# OnOnfre_dual_rev2.net
KiCad netlist of a schematic drawn in EAGLE
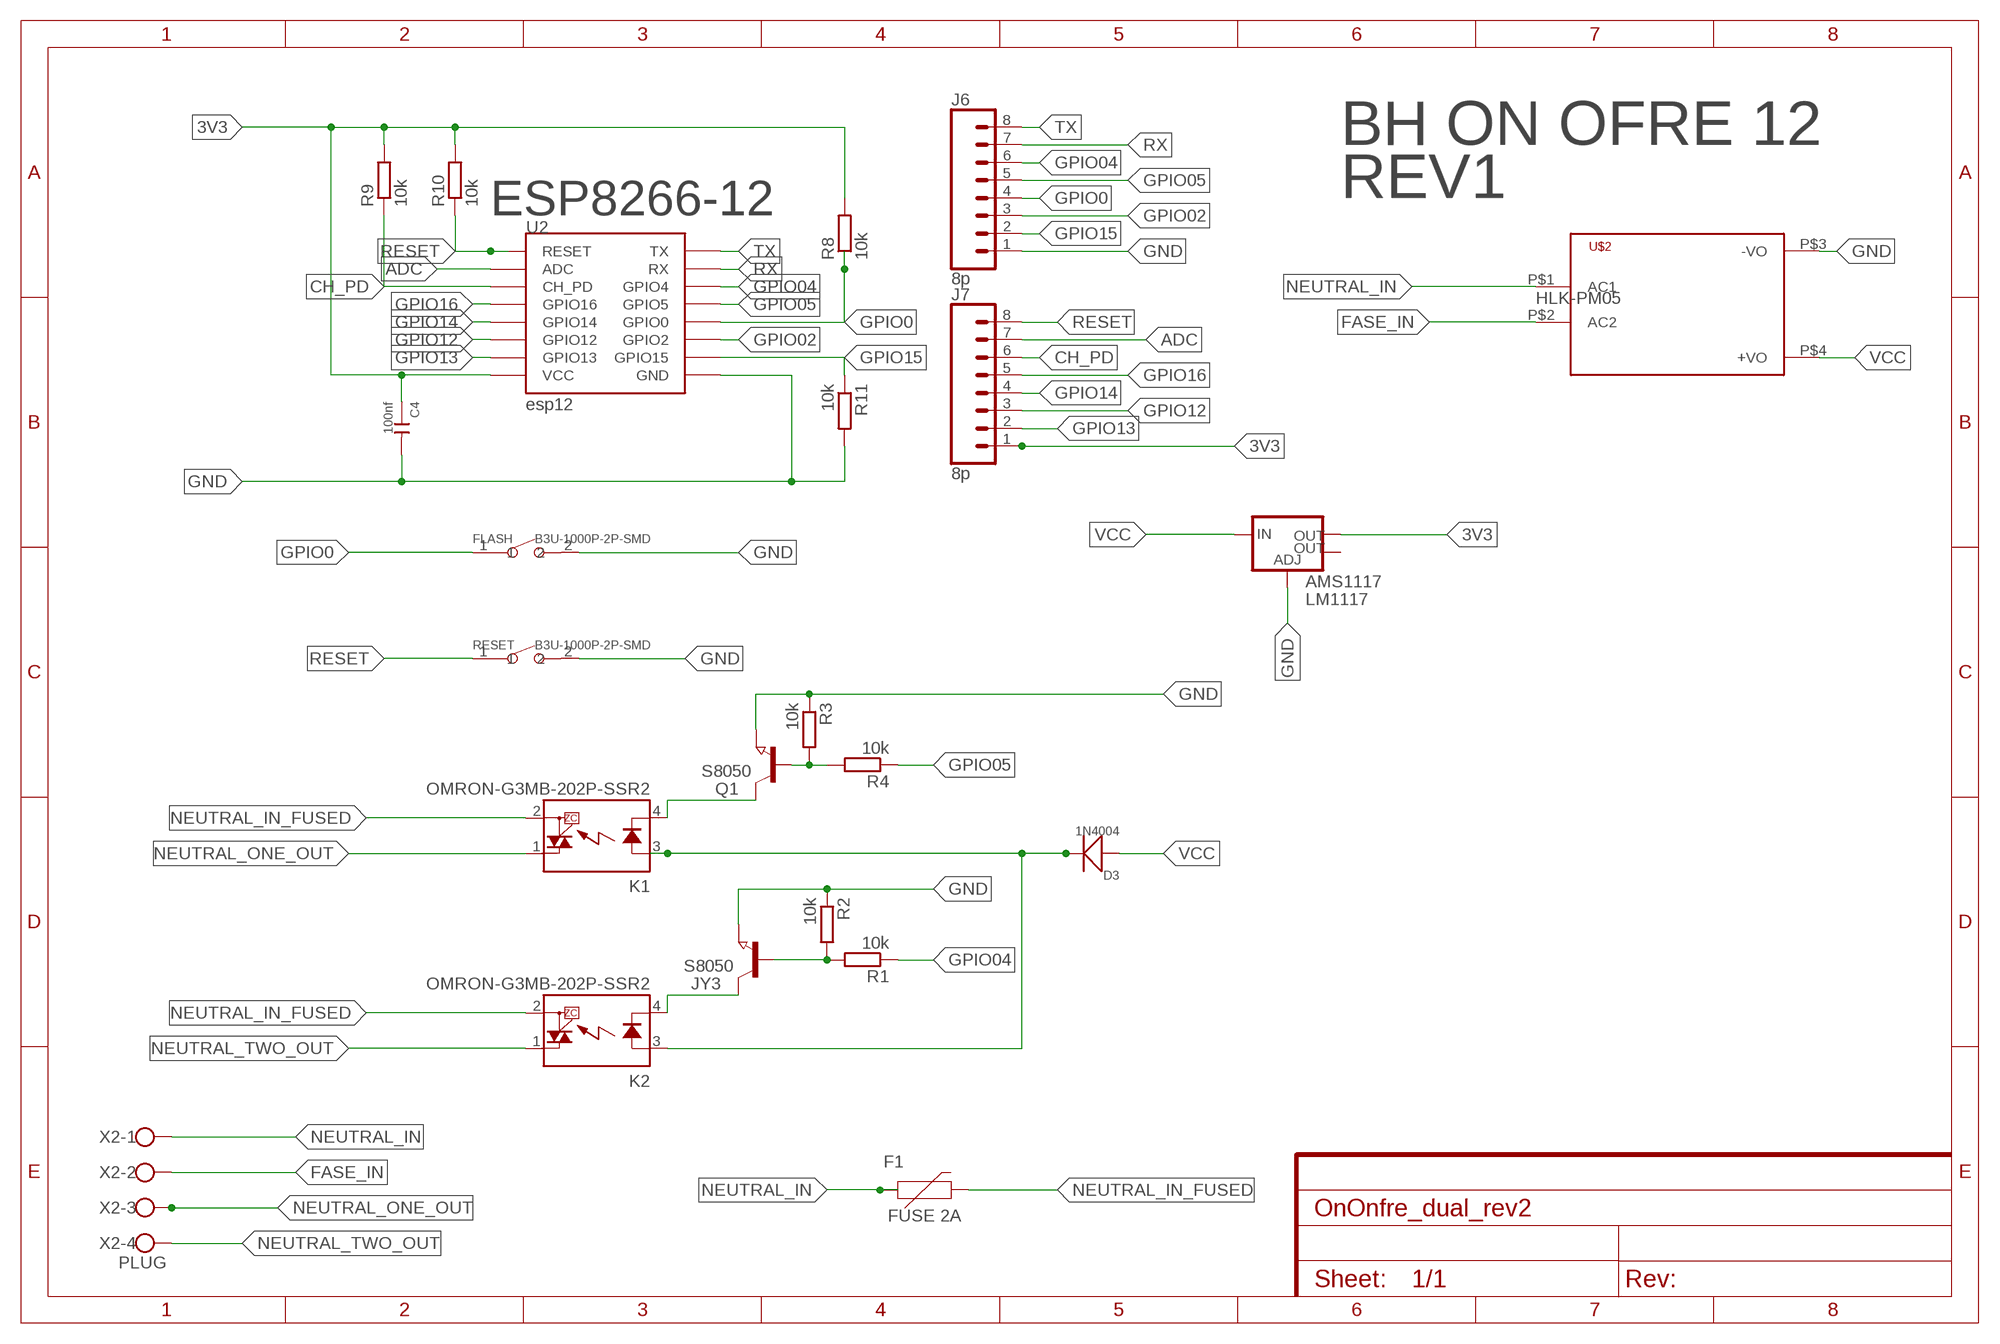
[diagram p0: schematic, sheet 1]

(export (version "E")
  (design (tool "Eeschema 10.0.6"))
  (components
    (comp (ref "AMS1117")
      (value "LM1117")
      (footprint "eagle-import:SOT223")
      (libsource (lib "eagle-import") (part "V_REG_LM1117SOT223"))
    )
    (comp (ref "C4")
      (value "100nf")
      (footprint "eagle-import:C0805")
      (fields (field (name "MPN") "CC0805KRX7R9BB104"))
      (libsource (lib "eagle-import") (part "CERAMIC-100NF-50V-10%-X7R(0805)"))
    )
    (comp (ref "D3")
      (value "1N4004")
      (footprint "eagle-import:DO-214AC")
      (fields (field (name "MPN") "1N4007"))
      (libsource (lib "eagle-import") (part "DIODE-GEN-PURPOSE-1KV-1A(DO-214AC)"))
    )
    (comp (ref "F1")
      (value "FUSE 2A")
      (footprint "eagle-import:PTH")
      (libsource (lib "eagle-import") (part "PPTC_PTH"))
    )
    (comp (ref "FLASH")
      (value "B3U-1000P-2P-SMD")
      (footprint "eagle-import:SW2-2.6-3.0X2.5X1.2+0.4MM")
      (libsource (lib "eagle-import") (part "SMD-BUTTON(2P-3.0X2.5X1.2+0.4MM)-B3U-1000P-2P-SMD"))
    )
    (comp (ref "J6")
      (value "8p")
      (footprint "eagle-import:1X08")
      (libsource (lib "eagle-import") (part "CONN_08{dblquote}"))
    )
    (comp (ref "J7")
      (value "8p")
      (footprint "eagle-import:1X08")
      (libsource (lib "eagle-import") (part "CONN_08{dblquote}"))
    )
    (comp (ref "JY3")
      (value "S8050")
      (footprint "eagle-import:SOT23")
      (libsource (lib "eagle-import") (part "NPN-TRANSISTOR_SOT23"))
    )
    (comp (ref "K1")
      (value "OMRON-G3MB-202P-SSR2")
      (footprint "eagle-import:OMRON-G3MB-202P-SSR")
      (fields (field (name "MPN") "S202S02F"))
      (libsource (lib "eagle-import") (part "OMRON-G3MB-202P-SSR2"))
    )
    (comp (ref "K2")
      (value "OMRON-G3MB-202P-SSR2")
      (footprint "eagle-import:OMRON-G3MB-202P-SSR")
      (fields (field (name "MPN") "S202S02F"))
      (libsource (lib "eagle-import") (part "OMRON-G3MB-202P-SSR2"))
    )
    (comp (ref "Q1")
      (value "S8050")
      (footprint "eagle-import:SOT23")
      (libsource (lib "eagle-import") (part "NPN-TRANSISTOR_SOT23"))
    )
    (comp (ref "R1")
      (value "10k")
      (footprint "eagle-import:R0603")
      (libsource (lib "eagle-import") (part "R-EU_R0603"))
    )
    (comp (ref "R2")
      (value "10k")
      (footprint "eagle-import:R0603")
      (libsource (lib "eagle-import") (part "R-EU_R0603"))
    )
    (comp (ref "R3")
      (value "10k")
      (footprint "eagle-import:R0603")
      (libsource (lib "eagle-import") (part "R-EU_R0603"))
    )
    (comp (ref "R4")
      (value "10k")
      (footprint "eagle-import:R0603")
      (libsource (lib "eagle-import") (part "R-EU_R0603"))
    )
    (comp (ref "R8")
      (value "10k")
      (footprint "eagle-import:R0603")
      (libsource (lib "eagle-import") (part "R-EU_R0603"))
    )
    (comp (ref "R9")
      (value "10k")
      (footprint "eagle-import:R0603")
      (libsource (lib "eagle-import") (part "R-EU_R0603"))
    )
    (comp (ref "R10")
      (value "10k")
      (footprint "eagle-import:R0603")
      (libsource (lib "eagle-import") (part "R-EU_R0603"))
    )
    (comp (ref "R11")
      (value "10k")
      (footprint "eagle-import:R0603")
      (libsource (lib "eagle-import") (part "R-EU_R0603"))
    )
    (comp (ref "RESET")
      (value "B3U-1000P-2P-SMD")
      (footprint "eagle-import:SW2-2.6-3.0X2.5X1.2+0.4MM")
      (libsource (lib "eagle-import") (part "SMD-BUTTON(2P-3.0X2.5X1.2+0.4MM)-B3U-1000P-2P-SMD"))
    )
    (comp (ref "U$2")
      (value "HKLPM01")
      (footprint "eagle-import:HKLPM01")
      (libsource (lib "eagle-import") (part "HKLPM01"))
    )
    (comp (ref "U2")
      (value "esp12")
      (footprint "eagle-import:ESP12-SMD")
      (libsource (lib "eagle-import") (part "ESP12SMD"))
    )
    (comp (ref "X2")
      (value "PLUG")
      (footprint "eagle-import:W237-4")
      (libsource (lib "eagle-import") (part "W237-4"))
    )
  )
  (nets
    (net (code "1") (name "3V3") (class "Default")
      (node (ref "AMS1117") (pin "2") (pinfunction "OUT_2") (pintype "output"))
      (node (ref "C4") (pin "1") (pinfunction "1_1") (pintype "passive"))
      (node (ref "J7") (pin "1") (pinfunction "1_1") (pintype "passive"))
      (node (ref "R10") (pin "2") (pinfunction "2_2") (pintype "passive"))
      (node (ref "R8") (pin "2") (pinfunction "2_2") (pintype "passive"))
      (node (ref "R9") (pin "2") (pinfunction "2_2") (pintype "passive"))
      (node (ref "U2") (pin "VCC") (pinfunction "VCC_VCC") (pintype "bidirectional"))
    )
    (net (code "2") (name "ADC") (class "Default")
      (node (ref "J7") (pin "7") (pinfunction "7_7") (pintype "passive"))
      (node (ref "U2") (pin "ADC") (pinfunction "ADC_ADC") (pintype "bidirectional"))
    )
    (net (code "3") (name "CH_PD") (class "Default")
      (node (ref "J7") (pin "6") (pinfunction "6_6") (pintype "passive"))
      (node (ref "R9") (pin "1") (pinfunction "1_1") (pintype "passive"))
      (node (ref "U2") (pin "CH_PD") (pinfunction "CH_PD_CH_PD") (pintype "bidirectional"))
    )
    (net (code "4") (name "FASE_IN") (class "Default")
      (node (ref "U$2") (pin "P$2") (pinfunction "AC2_P$2") (pintype "bidirectional"))
      (node (ref "X2") (pin "2") (pinfunction "KL_2") (pintype "passive"))
    )
    (net (code "5") (name "GND") (class "Default")
      (node (ref "AMS1117") (pin "1") (pinfunction "ADJ_1") (pintype "input"))
      (node (ref "C4") (pin "2") (pinfunction "2_2") (pintype "passive"))
      (node (ref "FLASH") (pin "2") (pinfunction "2_2") (pintype "bidirectional"))
      (node (ref "J6") (pin "1") (pinfunction "1_1") (pintype "passive"))
      (node (ref "JY3") (pin "2") (pinfunction "E_2") (pintype "passive"))
      (node (ref "Q1") (pin "2") (pinfunction "E_2") (pintype "passive"))
      (node (ref "R11") (pin "2") (pinfunction "2_2") (pintype "passive"))
      (node (ref "R2") (pin "1") (pinfunction "1_1") (pintype "passive"))
      (node (ref "R3") (pin "1") (pinfunction "1_1") (pintype "passive"))
      (node (ref "RESET") (pin "2") (pinfunction "2_2") (pintype "bidirectional"))
      (node (ref "U$2") (pin "P$3") (pinfunction "-VO_P$3") (pintype "bidirectional"))
      (node (ref "U2") (pin "GND") (pinfunction "GND_GND") (pintype "bidirectional"))
    )
    (net (code "6") (name "GPIO0") (class "Default")
      (node (ref "FLASH") (pin "1") (pinfunction "1_1") (pintype "bidirectional"))
      (node (ref "J6") (pin "4") (pinfunction "4_4") (pintype "passive"))
      (node (ref "R8") (pin "1") (pinfunction "1_1") (pintype "passive"))
      (node (ref "U2") (pin "GPIO0") (pinfunction "GPIO0_GPIO0") (pintype "bidirectional"))
    )
    (net (code "7") (name "GPIO02") (class "Default")
      (node (ref "J6") (pin "3") (pinfunction "3_3") (pintype "passive"))
      (node (ref "U2") (pin "GPIO2") (pinfunction "GPIO2_GPIO2") (pintype "bidirectional"))
    )
    (net (code "8") (name "GPIO04") (class "Default")
      (node (ref "J6") (pin "6") (pinfunction "6_6") (pintype "passive"))
      (node (ref "R1") (pin "1") (pinfunction "1_1") (pintype "passive"))
      (node (ref "U2") (pin "GPIO4") (pinfunction "GPIO4_GPIO4") (pintype "bidirectional"))
    )
    (net (code "9") (name "GPIO05") (class "Default")
      (node (ref "J6") (pin "5") (pinfunction "5_5") (pintype "passive"))
      (node (ref "R4") (pin "1") (pinfunction "1_1") (pintype "passive"))
      (node (ref "U2") (pin "GPIO5") (pinfunction "GPIO5_GPIO5") (pintype "bidirectional"))
    )
    (net (code "10") (name "GPIO12") (class "Default")
      (node (ref "J7") (pin "3") (pinfunction "3_3") (pintype "passive"))
      (node (ref "U2") (pin "GPIO12") (pinfunction "GPIO12_GPIO12") (pintype "bidirectional"))
    )
    (net (code "11") (name "GPIO13") (class "Default")
      (node (ref "J7") (pin "2") (pinfunction "2_2") (pintype "passive"))
      (node (ref "U2") (pin "GPIO13") (pinfunction "GPIO13_GPIO13") (pintype "bidirectional"))
    )
    (net (code "12") (name "GPIO14") (class "Default")
      (node (ref "J7") (pin "4") (pinfunction "4_4") (pintype "passive"))
      (node (ref "U2") (pin "GPIO14") (pinfunction "GPIO14_GPIO14") (pintype "bidirectional"))
    )
    (net (code "13") (name "GPIO15") (class "Default")
      (node (ref "J6") (pin "2") (pinfunction "2_2") (pintype "passive"))
      (node (ref "R11") (pin "1") (pinfunction "1_1") (pintype "passive"))
      (node (ref "U2") (pin "GPIO15") (pinfunction "GPIO15_GPIO15") (pintype "bidirectional"))
    )
    (net (code "14") (name "GPIO16") (class "Default")
      (node (ref "J7") (pin "5") (pinfunction "5_5") (pintype "passive"))
      (node (ref "U2") (pin "GPIO16") (pinfunction "GPIO16_GPIO16") (pintype "bidirectional"))
    )
    (net (code "15") (name "NEUTRAL_IN") (class "Default")
      (node (ref "F1") (pin "P$1") (pinfunction "1_P$1") (pintype "bidirectional"))
      (node (ref "U$2") (pin "P$1") (pinfunction "AC1_P$1") (pintype "bidirectional"))
      (node (ref "X2") (pin "1") (pinfunction "KL_1") (pintype "passive"))
    )
    (net (code "16") (name "NEUTRAL_IN_FUSED") (class "Default")
      (node (ref "F1") (pin "P$2") (pinfunction "2_P$2") (pintype "bidirectional"))
      (node (ref "K1") (pin "2") (pinfunction "DS2_2") (pintype "passive"))
      (node (ref "K2") (pin "2") (pinfunction "DS2_2") (pintype "passive"))
    )
    (net (code "17") (name "NEUTRAL_ONE_OUT") (class "Default")
      (node (ref "K1") (pin "1") (pinfunction "DS1_1") (pintype "passive"))
      (node (ref "X2") (pin "3") (pinfunction "KL_3") (pintype "passive"))
    )
    (net (code "18") (name "NEUTRAL_TWO_OUT") (class "Default")
      (node (ref "K2") (pin "1") (pinfunction "DS1_1") (pintype "passive"))
      (node (ref "X2") (pin "4") (pinfunction "KL_4") (pintype "passive"))
    )
    (net (code "19") (name "Net-(D3--)") (class "Default")
      (node (ref "D3") (pin "2") (pinfunction "-_2") (pintype "passive"))
      (node (ref "K1") (pin "3") (pinfunction "A_3") (pintype "passive"))
      (node (ref "K2") (pin "3") (pinfunction "A_3") (pintype "passive"))
    )
    (net (code "20") (name "Net-(JY3-B)") (class "Default")
      (node (ref "JY3") (pin "1") (pinfunction "B_1") (pintype "passive"))
      (node (ref "R1") (pin "2") (pinfunction "2_2") (pintype "passive"))
      (node (ref "R2") (pin "2") (pinfunction "2_2") (pintype "passive"))
    )
    (net (code "21") (name "Net-(JY3-C)") (class "Default")
      (node (ref "JY3") (pin "3") (pinfunction "C_3") (pintype "passive"))
      (node (ref "K2") (pin "4") (pinfunction "K_4") (pintype "passive"))
    )
    (net (code "22") (name "Net-(K1-K)") (class "Default")
      (node (ref "K1") (pin "4") (pinfunction "K_4") (pintype "passive"))
      (node (ref "Q1") (pin "3") (pinfunction "C_3") (pintype "passive"))
    )
    (net (code "23") (name "Net-(Q1-B)") (class "Default")
      (node (ref "Q1") (pin "1") (pinfunction "B_1") (pintype "passive"))
      (node (ref "R3") (pin "2") (pinfunction "2_2") (pintype "passive"))
      (node (ref "R4") (pin "2") (pinfunction "2_2") (pintype "passive"))
    )
    (net (code "24") (name "RESET") (class "Default")
      (node (ref "J7") (pin "8") (pinfunction "8_8") (pintype "passive"))
      (node (ref "R10") (pin "1") (pinfunction "1_1") (pintype "passive"))
      (node (ref "RESET") (pin "1") (pinfunction "1_1") (pintype "bidirectional"))
      (node (ref "U2") (pin "RESET") (pinfunction "RESET_RESET") (pintype "bidirectional"))
    )
    (net (code "25") (name "RX") (class "Default")
      (node (ref "J6") (pin "7") (pinfunction "7_7") (pintype "passive"))
      (node (ref "U2") (pin "RXD0") (pinfunction "RX_RXD0") (pintype "bidirectional"))
    )
    (net (code "26") (name "TX") (class "Default")
      (node (ref "J6") (pin "8") (pinfunction "8_8") (pintype "passive"))
      (node (ref "U2") (pin "TXD0") (pinfunction "TX_TXD0") (pintype "bidirectional"))
    )
    (net (code "27") (name "VCC") (class "Default")
      (node (ref "AMS1117") (pin "3") (pinfunction "IN_3") (pintype "input"))
      (node (ref "D3") (pin "1") (pinfunction "+_1") (pintype "passive"))
      (node (ref "U$2") (pin "P$4") (pinfunction "+VO_P$4") (pintype "bidirectional"))
    )
    (net (code "28") (name "unconnected-(AMS1117-OUT-Pad4)") (class "Default")
      (node (ref "AMS1117") (pin "4") (pinfunction "OUT_4") (pintype "output"))
    )
  )
)
